# mcu.net
KiCad netlist of a schematic drawn in Altium Designer
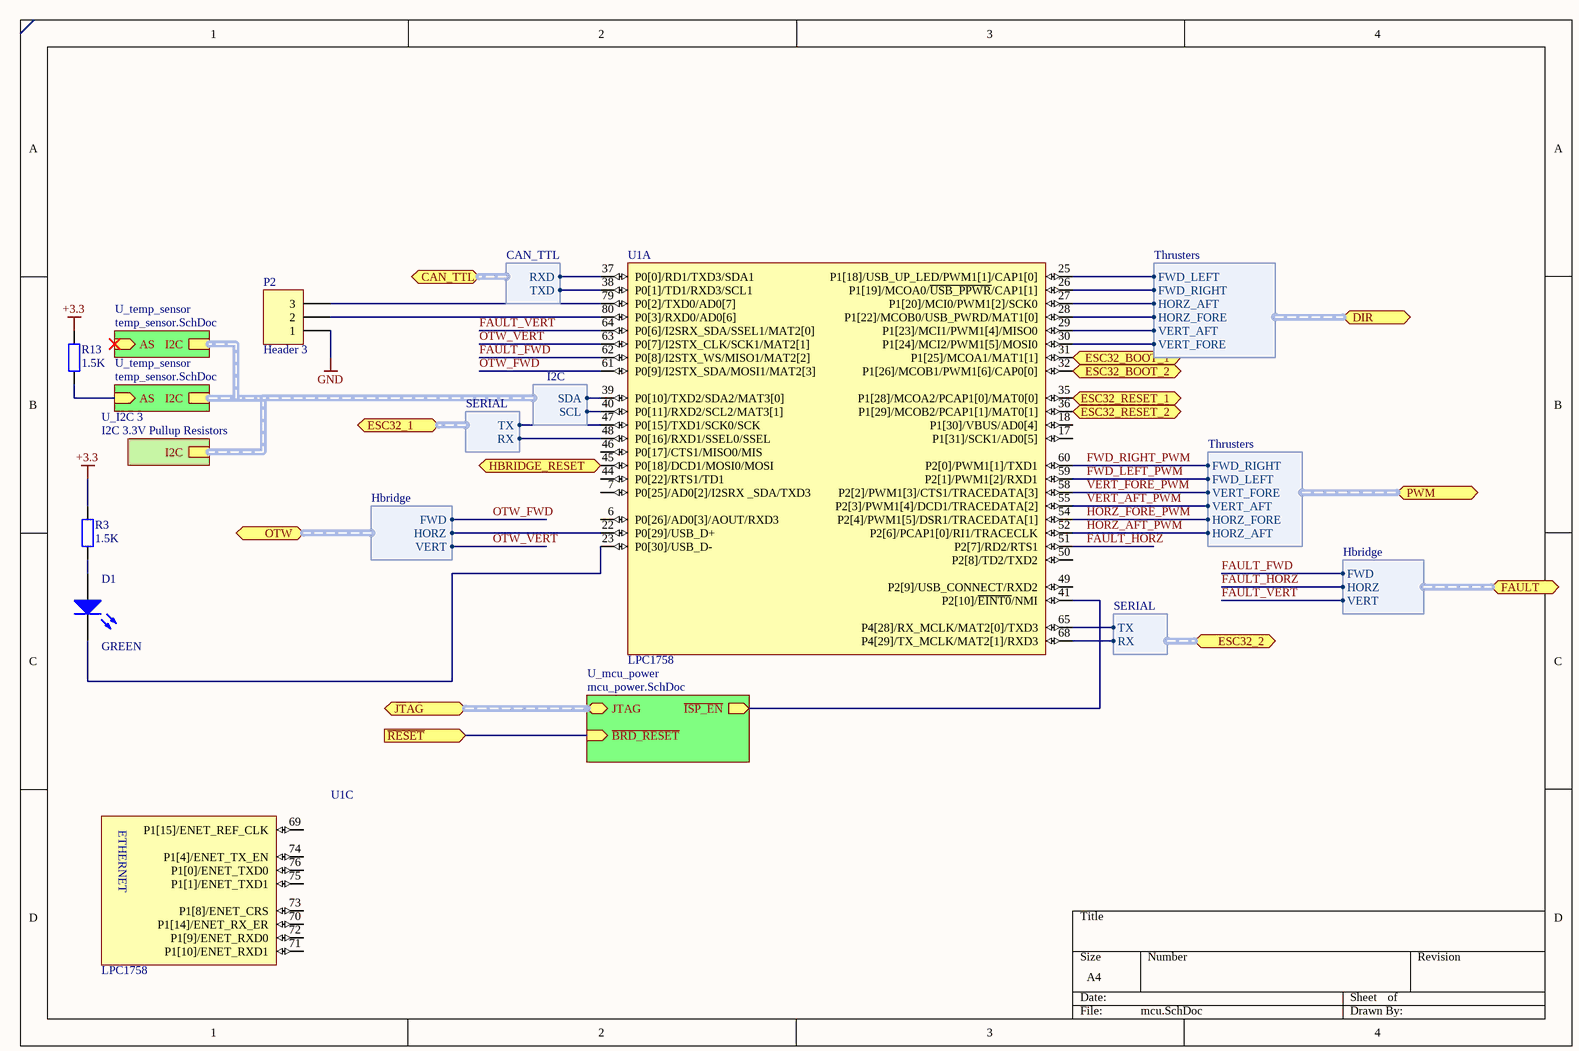
[diagram p0: mcu.SchDoc]

(export (version "E")
  (design (tool "Eeschema 10.0.6"))
  (components
    (comp (ref "D1")
      (value "GREEN")
      (footprint "LGQ971")
      (description "Typical RED, GREEN, YELLOW, AMBER GaAs LED")
      (libsource (lib "Miscellaneous Devices") (part "LED2"))
    )
    (comp (ref "P2")
      (value "Header 3")
      (footprint "HDR1X3")
      (description "Header, 3-Pin")
      (fields (field (name "PUBLISHER") "Altium Limited"))
      (libsource (lib "Miscellaneous Connectors") (part "Header 3"))
    )
    (comp (ref "R3")
      (value "1.5K")
      (footprint "R0603")
      (description "Resistor")
      (fields (field (name "Comment") "Res"))
      (libsource (lib "Miscellaneous Devices") (part "Res2"))
    )
    (comp (ref "R13")
      (value "1.5K")
      (footprint "R0603")
      (description "Resistor")
      (fields (field (name "Comment") "Res"))
      (libsource (lib "Miscellaneous Devices") (part "Res2"))
    )
    (comp (ref "U1")
      (value "LPC1758")
      (footprint "LPC1758FBD80")
      (description "NXP - LPC1758FBD80 - MCU, 32BIT, ARM CORTEX M3, 80LQFP")
      (libsource (lib "LPC1758") (part "LPC1758"))
    )
  )
  (nets
    (net (code "7") (name "+3.3") (class "Default")
      (node (ref "R13") (pin "2") (pinfunction "2_2") (pintype "passive"))
      (node (ref "R3") (pin "2") (pinfunction "2_2") (pintype "passive"))
    )
    (net (code "8") (name "/AS") (class "Default")
      (node (ref "R13") (pin "1") (pinfunction "1_1") (pintype "passive"))
    )
    (net (code "10") (name "/ESC32_BOOT_1") (class "Default")
      (node (ref "U1") (pin "31") (pinfunction "P1[25]/MCOA1/MAT1[1]_31") (pintype "bidirectional"))
    )
    (net (code "11") (name "/ESC32_BOOT_2") (class "Default")
      (node (ref "U1") (pin "32") (pinfunction "P1[26]/MCOB1/PWM1[6]/CAP0[0]_32") (pintype "bidirectional"))
    )
    (net (code "12") (name "/ESC32_RESET_1") (class "Default")
      (node (ref "U1") (pin "35") (pinfunction "P1[28]/MCOA2/PCAP1[0]/MAT0[0]_35") (pintype "bidirectional"))
    )
    (net (code "13") (name "/ESC32_RESET_2") (class "Default")
      (node (ref "U1") (pin "36") (pinfunction "P1[29]/MCOB2/PCAP1[1]/MAT0[1]_36") (pintype "bidirectional"))
    )
    (net (code "14") (name "/FAULT_FWD") (class "Default")
      (node (ref "U1") (pin "62") (pinfunction "P0[8]/I2STX_WS/MISO1/MAT2[2]_62") (pintype "bidirectional"))
    )
    (net (code "15") (name "/FAULT_HORZ") (class "Default")
      (node (ref "U1") (pin "51") (pinfunction "P2[7]/RD2/RTS1_51") (pintype "bidirectional"))
    )
    (net (code "16") (name "/FAULT_VERT") (class "Default")
      (node (ref "U1") (pin "64") (pinfunction "P0[6]/I2SRX_SDA/SSEL1/MAT2[0]_64") (pintype "bidirectional"))
    )
    (net (code "17") (name "/FWD_LEFT_PWM") (class "Default")
      (node (ref "U1") (pin "59") (pinfunction "P2[1]/PWM1[2]/RXD1_59") (pintype "bidirectional"))
    )
    (net (code "18") (name "/FWD_RIGHT_PWM") (class "Default")
      (node (ref "U1") (pin "60") (pinfunction "P2[0]/PWM1[1]/TXD1_60") (pintype "bidirectional"))
    )
    (net (code "19") (name "/HBRIDGE_RESET") (class "Default")
      (node (ref "U1") (pin "45") (pinfunction "P0[18]/DCD1/MOSI0/MOSI_45") (pintype "bidirectional"))
    )
    (net (code "20") (name "/HORZ_AFT_PWM") (class "Default")
      (node (ref "U1") (pin "52") (pinfunction "P2[6]/PCAP1[0]/RI1/TRACECLK_52") (pintype "bidirectional"))
    )
    (net (code "21") (name "/HORZ_FORE_PWM") (class "Default")
      (node (ref "U1") (pin "54") (pinfunction "P2[4]/PWM1[5]/DSR1/TRACEDATA[1]_54") (pintype "bidirectional"))
    )
    (net (code "24") (name "/OTW_FWD") (class "Default")
      (node (ref "U1") (pin "61") (pinfunction "P0[9]/I2STX_SDA/MOSI1/MAT2[3]_61") (pintype "bidirectional"))
    )
    (net (code "25") (name "/OTW_VERT") (class "Default")
      (node (ref "U1") (pin "63") (pinfunction "P0[7]/I2STX_CLK/SCK1/MAT2[1]_63") (pintype "bidirectional"))
    )
    (net (code "26") (name "/RXD") (class "Default")
      (node (ref "U1") (pin "37") (pinfunction "P0[0]/RD1/TXD3/SDA1_37") (pintype "bidirectional"))
    )
    (net (code "27") (name "/SCL") (class "Default")
      (node (ref "U1") (pin "40") (pinfunction "P0[11]/RXD2/SCL2/MAT3[1]_40") (pintype "bidirectional"))
    )
    (net (code "28") (name "/SDA") (class "Default")
      (node (ref "U1") (pin "39") (pinfunction "P0[10]/TXD2/SDA2/MAT3[0]_39") (pintype "bidirectional"))
    )
    (net (code "29") (name "/TXD") (class "Default")
      (node (ref "U1") (pin "38") (pinfunction "P0[1]/TD1/RXD3/SCL1_38") (pintype "bidirectional"))
    )
    (net (code "30") (name "/VERT_AFT_PWM") (class "Default")
      (node (ref "U1") (pin "55") (pinfunction "P2[3]/PWM1[4]/DCD1/TRACEDATA[2]_55") (pintype "bidirectional"))
    )
    (net (code "31") (name "/VERT_FORE_PWM") (class "Default")
      (node (ref "U1") (pin "58") (pinfunction "P2[2]/PWM1[3]/CTS1/TRACEDATA[3]_58") (pintype "bidirectional"))
    )
    (net (code "37") (name "/~{ISP_EN}") (class "Default")
      (node (ref "U1") (pin "41") (pinfunction "P2[10]/~{EINT0}/NMI_41") (pintype "bidirectional"))
    )
    (net (code "39") (name "GND") (class "Default")
      (node (ref "P2") (pin "1") (pinfunction "1_1") (pintype "passive"))
    )
    (net (code "40") (name "Net-(D1-A)") (class "Default")
      (node (ref "D1") (pin "1") (pinfunction "A_1") (pintype "passive"))
      (node (ref "R3") (pin "1") (pinfunction "1_1") (pintype "passive"))
    )
    (net (code "41") (name "Net-(D1-K)") (class "Default")
      (node (ref "D1") (pin "2") (pinfunction "K_2") (pintype "passive"))
      (node (ref "U1") (pin "23") (pinfunction "P0[30]/USB_D-_23") (pintype "bidirectional"))
    )
    (net (code "42") (name "Net-(U1A-P0[2]{slash}TXD0{slash}AD0[7])") (class "Default")
      (node (ref "P2") (pin "3") (pinfunction "3_3") (pintype "passive"))
      (node (ref "U1") (pin "79") (pinfunction "P0[2]/TXD0/AD0[7]_79") (pintype "bidirectional"))
    )
    (net (code "43") (name "Net-(U1A-P0[3]{slash}RXD0{slash}AD0[6])") (class "Default")
      (node (ref "P2") (pin "2") (pinfunction "2_2") (pintype "passive"))
      (node (ref "U1") (pin "80") (pinfunction "P0[3]/RXD0/AD0[6]_80") (pintype "bidirectional"))
    )
    (net (code "44") (name "unconnected-(U1A-P0[15]{slash}TXD1{slash}SCK0{slash}SCK-Pad47)") (class "Default")
      (node (ref "U1") (pin "47") (pinfunction "P0[15]/TXD1/SCK0/SCK_47") (pintype "bidirectional"))
    )
    (net (code "45") (name "unconnected-(U1A-P0[16]{slash}RXD1{slash}SSEL0{slash}SSEL-Pad48)") (class "Default")
      (node (ref "U1") (pin "48") (pinfunction "P0[16]/RXD1/SSEL0/SSEL_48") (pintype "bidirectional"))
    )
    (net (code "46") (name "unconnected-(U1A-P0[17]{slash}CTS1{slash}MISO0{slash}MIS-Pad46)") (class "Default")
      (node (ref "U1") (pin "46") (pinfunction "P0[17]/CTS1/MISO0/MIS_46") (pintype "bidirectional"))
    )
    (net (code "47") (name "unconnected-(U1A-P0[22]{slash}RTS1{slash}TD1-Pad44)") (class "Default")
      (node (ref "U1") (pin "44") (pinfunction "P0[22]/RTS1/TD1_44") (pintype "bidirectional"))
    )
    (net (code "48") (name "unconnected-(U1A-P0[25]{slash}AD0[2]{slash}I2SRX__SDA{slash}TXD3-Pad7)") (class "Default")
      (node (ref "U1") (pin "7") (pinfunction "P0[25]/AD0[2]/I2SRX__SDA/TXD3_7") (pintype "bidirectional"))
    )
    (net (code "49") (name "unconnected-(U1A-P0[26]{slash}AD0[3]{slash}AOUT{slash}RXD3-Pad6)") (class "Default")
      (node (ref "U1") (pin "6") (pinfunction "P0[26]/AD0[3]/AOUT/RXD3_6") (pintype "bidirectional"))
    )
    (net (code "50") (name "unconnected-(U1A-P0[29]{slash}USB_D+-Pad22)") (class "Default")
      (node (ref "U1") (pin "22") (pinfunction "P0[29]/USB_D+_22") (pintype "bidirectional"))
    )
    (net (code "51") (name "unconnected-(U1A-P1[18]{slash}USB_UP_LED{slash}PWM1[1]{slash}CAP1[0]-Pad25)") (class "Default")
      (node (ref "U1") (pin "25") (pinfunction "P1[18]/USB_UP_LED/PWM1[1]/CAP1[0]_25") (pintype "bidirectional"))
    )
    (net (code "52") (name "unconnected-(U1A-P1[19]{slash}MCOA0{slash}~{USB_PPWR}{slash}CAP1[1]-Pad26)") (class "Default")
      (node (ref "U1") (pin "26") (pinfunction "P1[19]/MCOA0/~{USB_PPWR}/CAP1[1]_26") (pintype "bidirectional"))
    )
    (net (code "53") (name "unconnected-(U1A-P1[20]{slash}MCI0{slash}PWM1[2]{slash}SCK0-Pad27)") (class "Default")
      (node (ref "U1") (pin "27") (pinfunction "P1[20]/MCI0/PWM1[2]/SCK0_27") (pintype "bidirectional"))
    )
    (net (code "54") (name "unconnected-(U1A-P1[22]{slash}MCOB0{slash}USB_PWRD{slash}MAT1[0]-Pad28)") (class "Default")
      (node (ref "U1") (pin "28") (pinfunction "P1[22]/MCOB0/USB_PWRD/MAT1[0]_28") (pintype "bidirectional"))
    )
    (net (code "55") (name "unconnected-(U1A-P1[23]{slash}MCI1{slash}PWM1[4]{slash}MISO0-Pad29)") (class "Default")
      (node (ref "U1") (pin "29") (pinfunction "P1[23]/MCI1/PWM1[4]/MISO0_29") (pintype "bidirectional"))
    )
    (net (code "56") (name "unconnected-(U1A-P1[24]{slash}MCI2{slash}PWM1[5]{slash}MOSI0-Pad30)") (class "Default")
      (node (ref "U1") (pin "30") (pinfunction "P1[24]/MCI2/PWM1[5]/MOSI0_30") (pintype "bidirectional"))
    )
    (net (code "57") (name "unconnected-(U1A-P1[30]{slash}VBUS{slash}AD0[4]-Pad18)") (class "Default")
      (node (ref "U1") (pin "18") (pinfunction "P1[30]/VBUS/AD0[4]_18") (pintype "bidirectional"))
    )
    (net (code "58") (name "unconnected-(U1A-P1[31]{slash}SCK1{slash}AD0[5]-Pad17)") (class "Default")
      (node (ref "U1") (pin "17") (pinfunction "P1[31]/SCK1/AD0[5]_17") (pintype "bidirectional"))
    )
    (net (code "59") (name "unconnected-(U1A-P2[8]{slash}TD2{slash}TXD2-Pad50)") (class "Default")
      (node (ref "U1") (pin "50") (pinfunction "P2[8]/TD2/TXD2_50") (pintype "bidirectional"))
    )
    (net (code "60") (name "unconnected-(U1A-P2[9]{slash}USB_CONNECT{slash}RXD2-Pad49)") (class "Default")
      (node (ref "U1") (pin "49") (pinfunction "P2[9]/USB_CONNECT/RXD2_49") (pintype "bidirectional"))
    )
    (net (code "61") (name "unconnected-(U1A-P4[28]{slash}RX_MCLK{slash}MAT2[0]{slash}TXD3-Pad65)") (class "Default")
      (node (ref "U1") (pin "65") (pinfunction "P4[28]/RX_MCLK/MAT2[0]/TXD3_65") (pintype "bidirectional"))
    )
    (net (code "62") (name "unconnected-(U1A-P4[29]{slash}TX_MCLK{slash}MAT2[1]{slash}RXD3-Pad68)") (class "Default")
      (node (ref "U1") (pin "68") (pinfunction "P4[29]/TX_MCLK/MAT2[1]/RXD3_68") (pintype "bidirectional"))
    )
    (net (code "63") (name "unconnected-(U1C-P1[0]{slash}ENET_TXD0-Pad76)") (class "Default")
      (node (ref "U1") (pin "76") (pinfunction "P1[0]/ENET_TXD0_76") (pintype "bidirectional"))
    )
    (net (code "64") (name "unconnected-(U1C-P1[1]{slash}ENET_TXD1-Pad75)") (class "Default")
      (node (ref "U1") (pin "75") (pinfunction "P1[1]/ENET_TXD1_75") (pintype "bidirectional"))
    )
    (net (code "65") (name "unconnected-(U1C-P1[4]{slash}ENET_TX_EN-Pad74)") (class "Default")
      (node (ref "U1") (pin "74") (pinfunction "P1[4]/ENET_TX_EN_74") (pintype "bidirectional"))
    )
    (net (code "66") (name "unconnected-(U1C-P1[8]{slash}ENET_CRS-Pad73)") (class "Default")
      (node (ref "U1") (pin "73") (pinfunction "P1[8]/ENET_CRS_73") (pintype "bidirectional"))
    )
    (net (code "67") (name "unconnected-(U1C-P1[9]{slash}ENET_RXD0-Pad72)") (class "Default")
      (node (ref "U1") (pin "72") (pinfunction "P1[9]/ENET_RXD0_72") (pintype "bidirectional"))
    )
    (net (code "68") (name "unconnected-(U1C-P1[10]{slash}ENET_RXD1-Pad71)") (class "Default")
      (node (ref "U1") (pin "71") (pinfunction "P1[10]/ENET_RXD1_71") (pintype "bidirectional"))
    )
    (net (code "69") (name "unconnected-(U1C-P1[14]{slash}ENET_RX_ER-Pad70)") (class "Default")
      (node (ref "U1") (pin "70") (pinfunction "P1[14]/ENET_RX_ER_70") (pintype "bidirectional"))
    )
    (net (code "70") (name "unconnected-(U1C-P1[15]{slash}ENET_REF_CLK-Pad69)") (class "Default")
      (node (ref "U1") (pin "69") (pinfunction "P1[15]/ENET_REF_CLK_69") (pintype "bidirectional"))
    )
  )
)
